# plata_sredn.net
KiCad netlist of a schematic drawn in Altium Designer
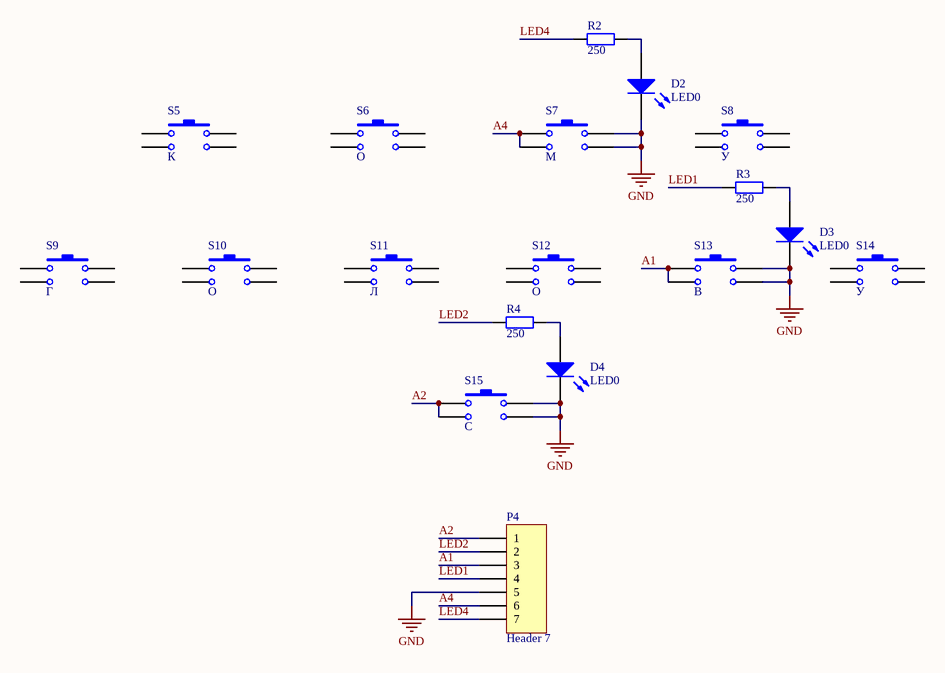
[diagram p0: plata_sredn.SchDoc]

(export (version "E")
  (design (tool "Eeschema 10.0.6"))
  (components
    (comp (ref "D2")
      (value "LED0")
      (footprint "LED0805")
      (description "Typical INFRARED GaAs LED")
      (fields (field (name "PUBLISHER") "Altium Limited"))
      (libsource (lib "Library") (part "LED0"))
    )
    (comp (ref "D3")
      (value "LED0")
      (footprint "LED0805")
      (description "Typical INFRARED GaAs LED")
      (fields (field (name "PUBLISHER") "Altium Limited"))
      (libsource (lib "Library") (part "LED0"))
    )
    (comp (ref "D4")
      (value "LED0")
      (footprint "LED0805")
      (description "Typical INFRARED GaAs LED")
      (fields (field (name "PUBLISHER") "Altium Limited"))
      (libsource (lib "Library") (part "LED0"))
    )
    (comp (ref "P4")
      (value "Header 7")
      (footprint "HDR1X7")
      (description "Header, 7-Pin")
      (fields (field (name "PUBLISHER") "Altium Limited"))
      (libsource (lib "Miscellaneous Connectors") (part "Header 7"))
    )
    (comp (ref "R2")
      (value "250")
      (footprint "6-0805_N")
      (description "Resistor")
      (fields (field (name "PUBLISHER") "Altium Limited"))
      (libsource (lib "Library") (part "Res2"))
    )
    (comp (ref "R3")
      (value "250")
      (footprint "6-0805_N")
      (description "Resistor")
      (fields (field (name "PUBLISHER") "Altium Limited"))
      (libsource (lib "Library") (part "Res2"))
    )
    (comp (ref "R4")
      (value "250")
      (footprint "6-0805_N")
      (description "Resistor")
      (fields (field (name "PUBLISHER") "Altium Limited"))
      (libsource (lib "Library") (part "Res2"))
    )
    (comp (ref "S5")
      (value "К")
      (footprint "STMW")
      (description "Switch")
      (fields (field (name "PUBLISHER") "Altium Limited"))
      (libsource (lib "Library") (part "STMW"))
    )
    (comp (ref "S6")
      (value "О")
      (footprint "STMW")
      (description "Switch")
      (fields (field (name "PUBLISHER") "Altium Limited"))
      (libsource (lib "Library") (part "STMW"))
    )
    (comp (ref "S7")
      (value "М")
      (footprint "STMW")
      (description "Switch")
      (fields (field (name "PUBLISHER") "Altium Limited"))
      (libsource (lib "Library") (part "STMW"))
    )
    (comp (ref "S8")
      (value "У")
      (footprint "STMW")
      (description "Switch")
      (fields (field (name "PUBLISHER") "Altium Limited"))
      (libsource (lib "Library") (part "STMW"))
    )
    (comp (ref "S9")
      (value "Г")
      (footprint "STMW")
      (description "Switch")
      (fields (field (name "PUBLISHER") "Altium Limited"))
      (libsource (lib "Library") (part "STMW"))
    )
    (comp (ref "S10")
      (value "О")
      (footprint "STMW")
      (description "Switch")
      (fields (field (name "PUBLISHER") "Altium Limited"))
      (libsource (lib "Library") (part "STMW"))
    )
    (comp (ref "S11")
      (value "Л")
      (footprint "STMW")
      (description "Switch")
      (fields (field (name "PUBLISHER") "Altium Limited"))
      (libsource (lib "Library") (part "STMW"))
    )
    (comp (ref "S12")
      (value "О")
      (footprint "STMW")
      (description "Switch")
      (fields (field (name "PUBLISHER") "Altium Limited"))
      (libsource (lib "Library") (part "STMW"))
    )
    (comp (ref "S13")
      (value "В")
      (footprint "STMW")
      (description "Switch")
      (fields (field (name "PUBLISHER") "Altium Limited"))
      (libsource (lib "Library") (part "STMW"))
    )
    (comp (ref "S14")
      (value "У")
      (footprint "STMW")
      (description "Switch")
      (fields (field (name "PUBLISHER") "Altium Limited"))
      (libsource (lib "Library") (part "STMW"))
    )
    (comp (ref "S15")
      (value "С")
      (footprint "STMW")
      (description "Switch")
      (fields (field (name "PUBLISHER") "Altium Limited"))
      (libsource (lib "Library") (part "STMW"))
    )
  )
  (nets
    (net (code "1") (name "/A1") (class "Default")
      (node (ref "P4") (pin "3") (pinfunction "3_3") (pintype "passive"))
      (node (ref "S13") (pin "1") (pinfunction "1_1") (pintype "passive"))
    )
    (net (code "2") (name "/A2") (class "Default")
      (node (ref "P4") (pin "1") (pinfunction "1_1") (pintype "passive"))
      (node (ref "S15") (pin "1") (pinfunction "1_1") (pintype "passive"))
    )
    (net (code "3") (name "/A4") (class "Default")
      (node (ref "P4") (pin "6") (pinfunction "6_6") (pintype "passive"))
      (node (ref "S7") (pin "1") (pinfunction "1_1") (pintype "passive"))
    )
    (net (code "4") (name "/LED1") (class "Default")
      (node (ref "P4") (pin "4") (pinfunction "4_4") (pintype "passive"))
      (node (ref "R3") (pin "2") (pinfunction "2_2") (pintype "passive"))
    )
    (net (code "5") (name "/LED2") (class "Default")
      (node (ref "P4") (pin "2") (pinfunction "2_2") (pintype "passive"))
      (node (ref "R4") (pin "2") (pinfunction "2_2") (pintype "passive"))
    )
    (net (code "6") (name "/LED4") (class "Default")
      (node (ref "P4") (pin "7") (pinfunction "7_7") (pintype "passive"))
      (node (ref "R2") (pin "2") (pinfunction "2_2") (pintype "passive"))
    )
    (net (code "7") (name "GND") (class "Default")
      (node (ref "D2") (pin "2") (pinfunction "K_2") (pintype "passive"))
      (node (ref "D3") (pin "2") (pinfunction "K_2") (pintype "passive"))
      (node (ref "D4") (pin "2") (pinfunction "K_2") (pintype "passive"))
      (node (ref "P4") (pin "5") (pinfunction "5_5") (pintype "passive"))
      (node (ref "S13") (pin "2") (pinfunction "2_2") (pintype "passive"))
      (node (ref "S15") (pin "2") (pinfunction "2_2") (pintype "passive"))
      (node (ref "S7") (pin "2") (pinfunction "2_2") (pintype "passive"))
    )
    (net (code "8") (name "Net-(D2-A)") (class "Default")
      (node (ref "D2") (pin "1") (pinfunction "A_1") (pintype "passive"))
      (node (ref "R2") (pin "1") (pinfunction "1_1") (pintype "passive"))
    )
    (net (code "9") (name "Net-(D3-A)") (class "Default")
      (node (ref "D3") (pin "1") (pinfunction "A_1") (pintype "passive"))
      (node (ref "R3") (pin "1") (pinfunction "1_1") (pintype "passive"))
    )
    (net (code "10") (name "Net-(D4-A)") (class "Default")
      (node (ref "D4") (pin "1") (pinfunction "A_1") (pintype "passive"))
      (node (ref "R4") (pin "1") (pinfunction "1_1") (pintype "passive"))
    )
    (net (code "11") (name "unconnected-(S5-Pad1)") (class "Default")
      (node (ref "S5") (pin "1") (pinfunction "1_1") (pintype "passive"))
    )
    (net (code "12") (name "unconnected-(S5-Pad1)_1") (class "Default")
      (node (ref "S5") (pin "1") (pinfunction "1_1") (pintype "passive"))
    )
    (net (code "13") (name "unconnected-(S5-Pad2)") (class "Default")
      (node (ref "S5") (pin "2") (pinfunction "2_2") (pintype "passive"))
    )
    (net (code "14") (name "unconnected-(S5-Pad2)_1") (class "Default")
      (node (ref "S5") (pin "2") (pinfunction "2_2") (pintype "passive"))
    )
    (net (code "15") (name "unconnected-(S6-Pad1)") (class "Default")
      (node (ref "S6") (pin "1") (pinfunction "1_1") (pintype "passive"))
    )
    (net (code "16") (name "unconnected-(S6-Pad1)_1") (class "Default")
      (node (ref "S6") (pin "1") (pinfunction "1_1") (pintype "passive"))
    )
    (net (code "17") (name "unconnected-(S6-Pad2)") (class "Default")
      (node (ref "S6") (pin "2") (pinfunction "2_2") (pintype "passive"))
    )
    (net (code "18") (name "unconnected-(S6-Pad2)_1") (class "Default")
      (node (ref "S6") (pin "2") (pinfunction "2_2") (pintype "passive"))
    )
    (net (code "19") (name "unconnected-(S8-Pad1)") (class "Default")
      (node (ref "S8") (pin "1") (pinfunction "1_1") (pintype "passive"))
    )
    (net (code "20") (name "unconnected-(S8-Pad1)_1") (class "Default")
      (node (ref "S8") (pin "1") (pinfunction "1_1") (pintype "passive"))
    )
    (net (code "21") (name "unconnected-(S8-Pad2)") (class "Default")
      (node (ref "S8") (pin "2") (pinfunction "2_2") (pintype "passive"))
    )
    (net (code "22") (name "unconnected-(S8-Pad2)_1") (class "Default")
      (node (ref "S8") (pin "2") (pinfunction "2_2") (pintype "passive"))
    )
    (net (code "23") (name "unconnected-(S9-Pad1)") (class "Default")
      (node (ref "S9") (pin "1") (pinfunction "1_1") (pintype "passive"))
    )
    (net (code "24") (name "unconnected-(S9-Pad1)_1") (class "Default")
      (node (ref "S9") (pin "1") (pinfunction "1_1") (pintype "passive"))
    )
    (net (code "25") (name "unconnected-(S9-Pad2)") (class "Default")
      (node (ref "S9") (pin "2") (pinfunction "2_2") (pintype "passive"))
    )
    (net (code "26") (name "unconnected-(S9-Pad2)_1") (class "Default")
      (node (ref "S9") (pin "2") (pinfunction "2_2") (pintype "passive"))
    )
    (net (code "27") (name "unconnected-(S10-Pad1)") (class "Default")
      (node (ref "S10") (pin "1") (pinfunction "1_1") (pintype "passive"))
    )
    (net (code "28") (name "unconnected-(S10-Pad1)_1") (class "Default")
      (node (ref "S10") (pin "1") (pinfunction "1_1") (pintype "passive"))
    )
    (net (code "29") (name "unconnected-(S10-Pad2)") (class "Default")
      (node (ref "S10") (pin "2") (pinfunction "2_2") (pintype "passive"))
    )
    (net (code "30") (name "unconnected-(S10-Pad2)_1") (class "Default")
      (node (ref "S10") (pin "2") (pinfunction "2_2") (pintype "passive"))
    )
    (net (code "31") (name "unconnected-(S11-Pad1)") (class "Default")
      (node (ref "S11") (pin "1") (pinfunction "1_1") (pintype "passive"))
    )
    (net (code "32") (name "unconnected-(S11-Pad1)_1") (class "Default")
      (node (ref "S11") (pin "1") (pinfunction "1_1") (pintype "passive"))
    )
    (net (code "33") (name "unconnected-(S11-Pad2)") (class "Default")
      (node (ref "S11") (pin "2") (pinfunction "2_2") (pintype "passive"))
    )
    (net (code "34") (name "unconnected-(S11-Pad2)_1") (class "Default")
      (node (ref "S11") (pin "2") (pinfunction "2_2") (pintype "passive"))
    )
    (net (code "35") (name "unconnected-(S12-Pad1)") (class "Default")
      (node (ref "S12") (pin "1") (pinfunction "1_1") (pintype "passive"))
    )
    (net (code "36") (name "unconnected-(S12-Pad1)_1") (class "Default")
      (node (ref "S12") (pin "1") (pinfunction "1_1") (pintype "passive"))
    )
    (net (code "37") (name "unconnected-(S12-Pad2)") (class "Default")
      (node (ref "S12") (pin "2") (pinfunction "2_2") (pintype "passive"))
    )
    (net (code "38") (name "unconnected-(S12-Pad2)_1") (class "Default")
      (node (ref "S12") (pin "2") (pinfunction "2_2") (pintype "passive"))
    )
    (net (code "39") (name "unconnected-(S14-Pad1)") (class "Default")
      (node (ref "S14") (pin "1") (pinfunction "1_1") (pintype "passive"))
    )
    (net (code "40") (name "unconnected-(S14-Pad1)_1") (class "Default")
      (node (ref "S14") (pin "1") (pinfunction "1_1") (pintype "passive"))
    )
    (net (code "41") (name "unconnected-(S14-Pad2)") (class "Default")
      (node (ref "S14") (pin "2") (pinfunction "2_2") (pintype "passive"))
    )
    (net (code "42") (name "unconnected-(S14-Pad2)_1") (class "Default")
      (node (ref "S14") (pin "2") (pinfunction "2_2") (pintype "passive"))
    )
  )
)
